# 038.net
KiCad netlist of a schematic drawn in Altium Designer
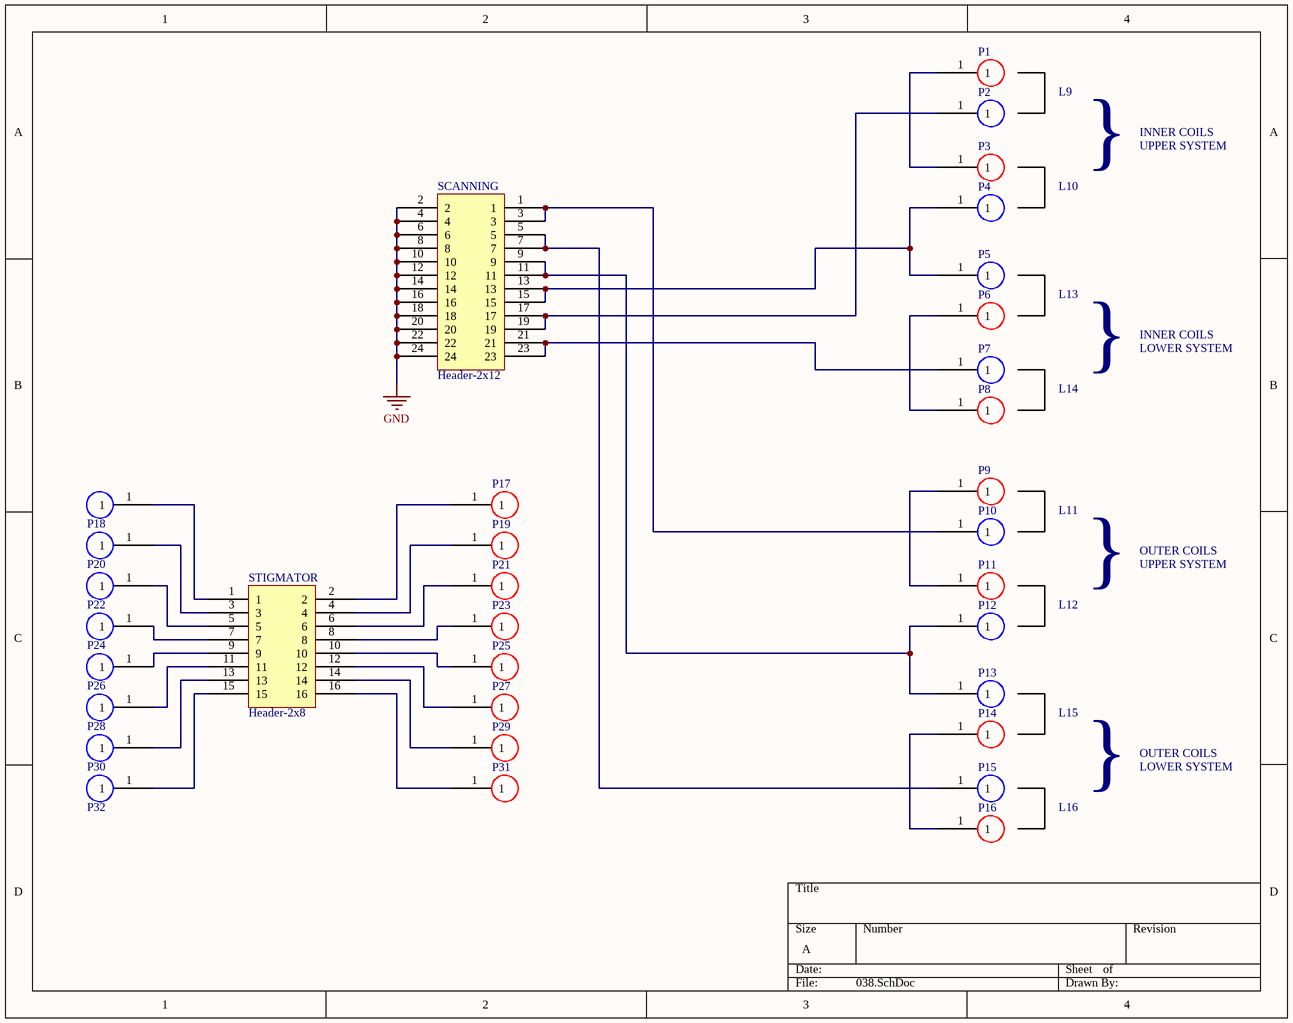
[diagram p0: 038.SchDoc]

(export (version "E")
  (design (tool "Eeschema 10.0.6"))
  (components
    (comp (ref "P1") (value "PINM") (footprint "PINM") (libsource (lib "OpenSEM") (part "PINM")))
    (comp (ref "P2") (value "PIN") (footprint "PIN") (libsource (lib "OpenSEM") (part "PIN")))
    (comp (ref "P3") (value "PINM") (footprint "PINM") (libsource (lib "OpenSEM") (part "PINM")))
    (comp (ref "P4") (value "PIN") (footprint "PIN") (libsource (lib "OpenSEM") (part "PIN")))
    (comp (ref "P5") (value "PIN") (footprint "PIN") (libsource (lib "OpenSEM") (part "PIN")))
    (comp (ref "P6") (value "PINM") (footprint "PINM") (libsource (lib "OpenSEM") (part "PINM")))
    (comp (ref "P7") (value "PIN") (footprint "PIN") (libsource (lib "OpenSEM") (part "PIN")))
    (comp (ref "P8") (value "PINM") (footprint "PINM") (libsource (lib "OpenSEM") (part "PINM")))
    (comp (ref "P9") (value "PINM") (footprint "PINM") (libsource (lib "OpenSEM") (part "PINM")))
    (comp (ref "P10") (value "PIN") (footprint "PIN") (libsource (lib "OpenSEM") (part "PIN")))
    (comp (ref "P11") (value "PINM") (footprint "PINM") (libsource (lib "OpenSEM") (part "PINM")))
    (comp (ref "P12") (value "PIN") (footprint "PIN") (libsource (lib "OpenSEM") (part "PIN")))
    (comp (ref "P13") (value "PIN") (footprint "PIN") (libsource (lib "OpenSEM") (part "PIN")))
    (comp (ref "P14") (value "PINM") (footprint "PINM") (libsource (lib "OpenSEM") (part "PINM")))
    (comp (ref "P15") (value "PIN") (footprint "PIN") (libsource (lib "OpenSEM") (part "PIN")))
    (comp (ref "P16") (value "PINM") (footprint "PINM") (libsource (lib "OpenSEM") (part "PINM")))
    (comp (ref "P17") (value "PINM") (footprint "PINM") (libsource (lib "OpenSEM") (part "PINM")))
    (comp (ref "P18") (value "PIN") (footprint "PIN") (libsource (lib "OpenSEM") (part "PIN")))
    (comp (ref "P19") (value "PINM") (footprint "PINM") (libsource (lib "OpenSEM") (part "PINM")))
    (comp (ref "P20") (value "PIN") (footprint "PIN") (libsource (lib "OpenSEM") (part "PIN")))
    (comp (ref "P21") (value "PINM") (footprint "PINM") (libsource (lib "OpenSEM") (part "PINM")))
    (comp (ref "P22") (value "PIN") (footprint "PIN") (libsource (lib "OpenSEM") (part "PIN")))
    (comp (ref "P23") (value "PINM") (footprint "PINM") (libsource (lib "OpenSEM") (part "PINM")))
    (comp (ref "P24") (value "PIN") (footprint "PIN") (libsource (lib "OpenSEM") (part "PIN")))
    (comp (ref "P25") (value "PINM") (footprint "PINM") (libsource (lib "OpenSEM") (part "PINM")))
    (comp (ref "P26") (value "PIN") (footprint "PIN") (libsource (lib "OpenSEM") (part "PIN")))
    (comp (ref "P27") (value "PINM") (footprint "PINM") (libsource (lib "OpenSEM") (part "PINM")))
    (comp (ref "P28") (value "PIN") (footprint "PIN") (libsource (lib "OpenSEM") (part "PIN")))
    (comp (ref "P29") (value "PINM") (footprint "PINM") (libsource (lib "OpenSEM") (part "PINM")))
    (comp (ref "P30") (value "PIN") (footprint "PIN") (libsource (lib "OpenSEM") (part "PIN")))
    (comp (ref "P31") (value "PINM") (footprint "PINM") (libsource (lib "OpenSEM") (part "PINM")))
    (comp (ref "P32") (value "PIN") (footprint "PIN") (libsource (lib "OpenSEM") (part "PIN")))
    (comp (ref "SCANNING")
      (value "Header-2x12")
      (footprint "scanning")
      (libsource (lib "VinisLab") (part "Header-2x12"))
    )
    (comp (ref "STIGMATOR")
      (value "Header-2x8")
      (footprint "STIGMATOR")
      (libsource (lib "VinisLab") (part "Header-2x8"))
    )
  )
  (nets
    (net (code "1") (name "GND") (class "Default")
      (node (ref "SCANNING") (pin "10") (pinfunction "10_10") (pintype "passive"))
      (node (ref "SCANNING") (pin "12") (pinfunction "12_12") (pintype "passive"))
      (node (ref "SCANNING") (pin "14") (pinfunction "14_14") (pintype "passive"))
      (node (ref "SCANNING") (pin "16") (pinfunction "16_16") (pintype "passive"))
      (node (ref "SCANNING") (pin "18") (pinfunction "18_18") (pintype "passive"))
      (node (ref "SCANNING") (pin "2") (pinfunction "2_2") (pintype "passive"))
      (node (ref "SCANNING") (pin "20") (pinfunction "20_20") (pintype "passive"))
      (node (ref "SCANNING") (pin "22") (pinfunction "22_22") (pintype "passive"))
      (node (ref "SCANNING") (pin "24") (pinfunction "24_24") (pintype "passive"))
      (node (ref "SCANNING") (pin "4") (pinfunction "4_4") (pintype "passive"))
      (node (ref "SCANNING") (pin "6") (pinfunction "6_6") (pintype "passive"))
      (node (ref "SCANNING") (pin "8") (pinfunction "8_8") (pintype "passive"))
    )
    (net (code "2") (name "Net-(P1-Pad1)") (class "Default")
      (node (ref "P1") (pin "1") (pinfunction "1_1") (pintype "passive"))
      (node (ref "P3") (pin "1") (pinfunction "1_1") (pintype "passive"))
    )
    (net (code "3") (name "Net-(P2-Pad1)") (class "Default")
      (node (ref "P2") (pin "1") (pinfunction "1_1") (pintype "passive"))
      (node (ref "SCANNING") (pin "17") (pinfunction "17_17") (pintype "passive"))
      (node (ref "SCANNING") (pin "19") (pinfunction "19_19") (pintype "passive"))
    )
    (net (code "4") (name "Net-(P4-Pad1)") (class "Default")
      (node (ref "P4") (pin "1") (pinfunction "1_1") (pintype "passive"))
      (node (ref "P5") (pin "1") (pinfunction "1_1") (pintype "passive"))
      (node (ref "SCANNING") (pin "13") (pinfunction "13_13") (pintype "passive"))
      (node (ref "SCANNING") (pin "15") (pinfunction "15_15") (pintype "passive"))
    )
    (net (code "5") (name "Net-(P6-Pad1)") (class "Default")
      (node (ref "P6") (pin "1") (pinfunction "1_1") (pintype "passive"))
      (node (ref "P8") (pin "1") (pinfunction "1_1") (pintype "passive"))
    )
    (net (code "6") (name "Net-(P7-Pad1)") (class "Default")
      (node (ref "P7") (pin "1") (pinfunction "1_1") (pintype "passive"))
      (node (ref "SCANNING") (pin "21") (pinfunction "21_21") (pintype "passive"))
      (node (ref "SCANNING") (pin "23") (pinfunction "23_23") (pintype "passive"))
    )
    (net (code "7") (name "Net-(P10-Pad1)") (class "Default")
      (node (ref "P10") (pin "1") (pinfunction "1_1") (pintype "passive"))
      (node (ref "SCANNING") (pin "1") (pinfunction "1_1") (pintype "passive"))
      (node (ref "SCANNING") (pin "3") (pinfunction "3_3") (pintype "passive"))
    )
    (net (code "8") (name "Net-(P11-Pad1)") (class "Default")
      (node (ref "P11") (pin "1") (pinfunction "1_1") (pintype "passive"))
      (node (ref "P9") (pin "1") (pinfunction "1_1") (pintype "passive"))
    )
    (net (code "9") (name "Net-(P12-Pad1)") (class "Default")
      (node (ref "P12") (pin "1") (pinfunction "1_1") (pintype "passive"))
      (node (ref "P13") (pin "1") (pinfunction "1_1") (pintype "passive"))
      (node (ref "SCANNING") (pin "11") (pinfunction "11_11") (pintype "passive"))
      (node (ref "SCANNING") (pin "9") (pinfunction "9_9") (pintype "passive"))
    )
    (net (code "10") (name "Net-(P14-Pad1)") (class "Default")
      (node (ref "P14") (pin "1") (pinfunction "1_1") (pintype "passive"))
      (node (ref "P16") (pin "1") (pinfunction "1_1") (pintype "passive"))
    )
    (net (code "11") (name "Net-(P15-Pad1)") (class "Default")
      (node (ref "P15") (pin "1") (pinfunction "1_1") (pintype "passive"))
      (node (ref "SCANNING") (pin "5") (pinfunction "5_5") (pintype "passive"))
      (node (ref "SCANNING") (pin "7") (pinfunction "7_7") (pintype "passive"))
    )
    (net (code "12") (name "Net-(P17-Pad1)") (class "Default")
      (node (ref "P17") (pin "1") (pinfunction "1_1") (pintype "passive"))
      (node (ref "STIGMATOR") (pin "2") (pinfunction "2_2") (pintype "passive"))
    )
    (net (code "13") (name "Net-(P18-Pad1)") (class "Default")
      (node (ref "P18") (pin "1") (pinfunction "1_1") (pintype "passive"))
      (node (ref "STIGMATOR") (pin "1") (pinfunction "1_1") (pintype "passive"))
    )
    (net (code "14") (name "Net-(P19-Pad1)") (class "Default")
      (node (ref "P19") (pin "1") (pinfunction "1_1") (pintype "passive"))
      (node (ref "STIGMATOR") (pin "4") (pinfunction "4_4") (pintype "passive"))
    )
    (net (code "15") (name "Net-(P20-Pad1)") (class "Default")
      (node (ref "P20") (pin "1") (pinfunction "1_1") (pintype "passive"))
      (node (ref "STIGMATOR") (pin "3") (pinfunction "3_3") (pintype "passive"))
    )
    (net (code "16") (name "Net-(P21-Pad1)") (class "Default")
      (node (ref "P21") (pin "1") (pinfunction "1_1") (pintype "passive"))
      (node (ref "STIGMATOR") (pin "6") (pinfunction "6_6") (pintype "passive"))
    )
    (net (code "17") (name "Net-(P22-Pad1)") (class "Default")
      (node (ref "P22") (pin "1") (pinfunction "1_1") (pintype "passive"))
      (node (ref "STIGMATOR") (pin "5") (pinfunction "5_5") (pintype "passive"))
    )
    (net (code "18") (name "Net-(P23-Pad1)") (class "Default")
      (node (ref "P23") (pin "1") (pinfunction "1_1") (pintype "passive"))
      (node (ref "STIGMATOR") (pin "8") (pinfunction "8_8") (pintype "passive"))
    )
    (net (code "19") (name "Net-(P24-Pad1)") (class "Default")
      (node (ref "P24") (pin "1") (pinfunction "1_1") (pintype "passive"))
      (node (ref "STIGMATOR") (pin "7") (pinfunction "7_7") (pintype "passive"))
    )
    (net (code "20") (name "Net-(P25-Pad1)") (class "Default")
      (node (ref "P25") (pin "1") (pinfunction "1_1") (pintype "passive"))
      (node (ref "STIGMATOR") (pin "10") (pinfunction "10_10") (pintype "passive"))
    )
    (net (code "21") (name "Net-(P26-Pad1)") (class "Default")
      (node (ref "P26") (pin "1") (pinfunction "1_1") (pintype "passive"))
      (node (ref "STIGMATOR") (pin "9") (pinfunction "9_9") (pintype "passive"))
    )
    (net (code "22") (name "Net-(P27-Pad1)") (class "Default")
      (node (ref "P27") (pin "1") (pinfunction "1_1") (pintype "passive"))
      (node (ref "STIGMATOR") (pin "12") (pinfunction "12_12") (pintype "passive"))
    )
    (net (code "23") (name "Net-(P28-Pad1)") (class "Default")
      (node (ref "P28") (pin "1") (pinfunction "1_1") (pintype "passive"))
      (node (ref "STIGMATOR") (pin "11") (pinfunction "11_11") (pintype "passive"))
    )
    (net (code "24") (name "Net-(P29-Pad1)") (class "Default")
      (node (ref "P29") (pin "1") (pinfunction "1_1") (pintype "passive"))
      (node (ref "STIGMATOR") (pin "14") (pinfunction "14_14") (pintype "passive"))
    )
    (net (code "25") (name "Net-(P30-Pad1)") (class "Default")
      (node (ref "P30") (pin "1") (pinfunction "1_1") (pintype "passive"))
      (node (ref "STIGMATOR") (pin "13") (pinfunction "13_13") (pintype "passive"))
    )
    (net (code "26") (name "Net-(P31-Pad1)") (class "Default")
      (node (ref "P31") (pin "1") (pinfunction "1_1") (pintype "passive"))
      (node (ref "STIGMATOR") (pin "16") (pinfunction "16_16") (pintype "passive"))
    )
    (net (code "27") (name "Net-(P32-Pad1)") (class "Default")
      (node (ref "P32") (pin "1") (pinfunction "1_1") (pintype "passive"))
      (node (ref "STIGMATOR") (pin "15") (pinfunction "15_15") (pintype "passive"))
    )
  )
)
